# v1.net
KiCad netlist of a schematic drawn in EAGLE
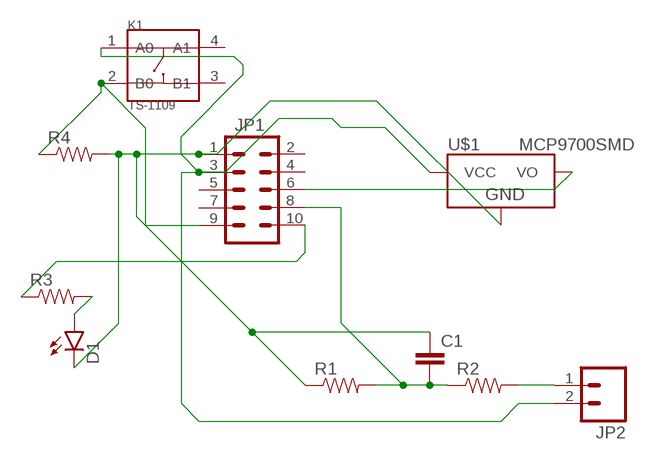
[diagram p0: schematic, sheet 1]

(export (version "E")
  (design (tool "Eeschema 10.0.6"))
  (components
    (comp (ref "C1")
      (value "CAP0805")
      (footprint "eagle-import:0805")
      (libsource (lib "eagle-import") (part "CAP0805"))
    )
    (comp (ref "D1")
      (value "LED1206")
      (footprint "eagle-import:LED-1206")
      (libsource (lib "eagle-import") (part "LED1206"))
    )
    (comp (ref "JP1")
      (value "M05X2PTH")
      (footprint "eagle-import:AVR_ICSP")
      (libsource (lib "eagle-import") (part "M05X2PTH"))
    )
    (comp (ref "JP2")
      (value "M02PTH")
      (footprint "eagle-import:1X02")
      (libsource (lib "eagle-import") (part "M02PTH"))
    )
    (comp (ref "K1")
      (value "TS-1109")
      (footprint "eagle-import:SW4-6.0X6.0X5.0MM")
      (libsource (lib "eagle-import") (part "DIP-BUTTON-4P"))
    )
    (comp (ref "R1")
      (value "RESISTOR0805-RES")
      (footprint "eagle-import:0805")
      (libsource (lib "eagle-import") (part "RESISTOR0805-RES"))
    )
    (comp (ref "R2")
      (value "RESISTOR0805-RES")
      (footprint "eagle-import:0805")
      (libsource (lib "eagle-import") (part "RESISTOR0805-RES"))
    )
    (comp (ref "R3")
      (value "RESISTOR0805-RES")
      (footprint "eagle-import:0805")
      (libsource (lib "eagle-import") (part "RESISTOR0805-RES"))
    )
    (comp (ref "R4")
      (value "RESISTOR0805-RES")
      (footprint "eagle-import:0805")
      (libsource (lib "eagle-import") (part "RESISTOR0805-RES"))
    )
    (comp (ref "U$1")
      (value "MCP9700SMD")
      (footprint "eagle-import:SOT23-3")
      (libsource (lib "eagle-import") (part "MCP9700SMD"))
    )
  )
  (nets
    (net (code "1") (name "Net-(C1-Pad2)") (class "Default")
      (node (ref "C1") (pin "2") (pinfunction "2_2") (pintype "passive"))
      (node (ref "JP1") (pin "8") (pinfunction "8_8") (pintype "passive"))
      (node (ref "R1") (pin "2") (pinfunction "2_2") (pintype "passive"))
      (node (ref "R2") (pin "1") (pinfunction "1_1") (pintype "passive"))
    )
    (net (code "2") (name "Net-(D1-PadA)") (class "Default")
      (node (ref "D1") (pin "A") (pinfunction "A_A") (pintype "passive"))
      (node (ref "R3") (pin "2") (pinfunction "2_2") (pintype "passive"))
    )
    (net (code "3") (name "Net-(JP1-Pad10)") (class "Default")
      (node (ref "JP1") (pin "10") (pinfunction "10_10") (pintype "passive"))
      (node (ref "R3") (pin "1") (pinfunction "1_1") (pintype "passive"))
    )
    (net (code "4") (name "Net-(JP2-Pad1)") (class "Default")
      (node (ref "JP2") (pin "1") (pinfunction "1_1") (pintype "passive"))
      (node (ref "R2") (pin "2") (pinfunction "2_2") (pintype "passive"))
    )
    (net (code "5") (name "Net-(K1-A0)") (class "Default")
      (node (ref "JP1") (pin "3") (pinfunction "3_3") (pintype "passive"))
      (node (ref "JP2") (pin "2") (pinfunction "2_2") (pintype "passive"))
      (node (ref "K1") (pin "1") (pinfunction "A0_1") (pintype "bidirectional"))
      (node (ref "U$1") (pin "1") (pinfunction "VCC_1") (pintype "bidirectional"))
    )
    (net (code "6") (name "Net-(K1-B0)") (class "Default")
      (node (ref "JP1") (pin "9") (pinfunction "9_9") (pintype "passive"))
      (node (ref "K1") (pin "2") (pinfunction "B0_2") (pintype "bidirectional"))
      (node (ref "R4") (pin "1") (pinfunction "1_1") (pintype "passive"))
    )
    (net (code "7") (name "Net-(U$1-GND)") (class "Default")
      (node (ref "C1") (pin "1") (pinfunction "1_1") (pintype "passive"))
      (node (ref "D1") (pin "C") (pinfunction "C_C") (pintype "passive"))
      (node (ref "JP1") (pin "1") (pinfunction "1_1") (pintype "passive"))
      (node (ref "R1") (pin "1") (pinfunction "1_1") (pintype "passive"))
      (node (ref "R4") (pin "2") (pinfunction "2_2") (pintype "passive"))
      (node (ref "U$1") (pin "3") (pinfunction "GND_3") (pintype "bidirectional"))
    )
    (net (code "8") (name "Net-(U$1-VO)") (class "Default")
      (node (ref "JP1") (pin "6") (pinfunction "6_6") (pintype "passive"))
      (node (ref "U$1") (pin "2") (pinfunction "VO_2") (pintype "bidirectional"))
    )
    (net (code "9") (name "unconnected-(JP1-Pad2)") (class "Default")
      (node (ref "JP1") (pin "2") (pinfunction "2_2") (pintype "passive"))
    )
    (net (code "10") (name "unconnected-(JP1-Pad4)") (class "Default")
      (node (ref "JP1") (pin "4") (pinfunction "4_4") (pintype "passive"))
    )
    (net (code "11") (name "unconnected-(JP1-Pad5)") (class "Default")
      (node (ref "JP1") (pin "5") (pinfunction "5_5") (pintype "passive"))
    )
    (net (code "12") (name "unconnected-(JP1-Pad7)") (class "Default")
      (node (ref "JP1") (pin "7") (pinfunction "7_7") (pintype "passive"))
    )
    (net (code "13") (name "unconnected-(K1-A1-Pad4)") (class "Default")
      (node (ref "K1") (pin "4") (pinfunction "A1_4") (pintype "bidirectional"))
    )
    (net (code "14") (name "unconnected-(K1-B1-Pad3)") (class "Default")
      (node (ref "K1") (pin "3") (pinfunction "B1_3") (pintype "bidirectional"))
    )
  )
)
